# outdoor_module.net
KiCad netlist of a schematic drawn in EAGLE
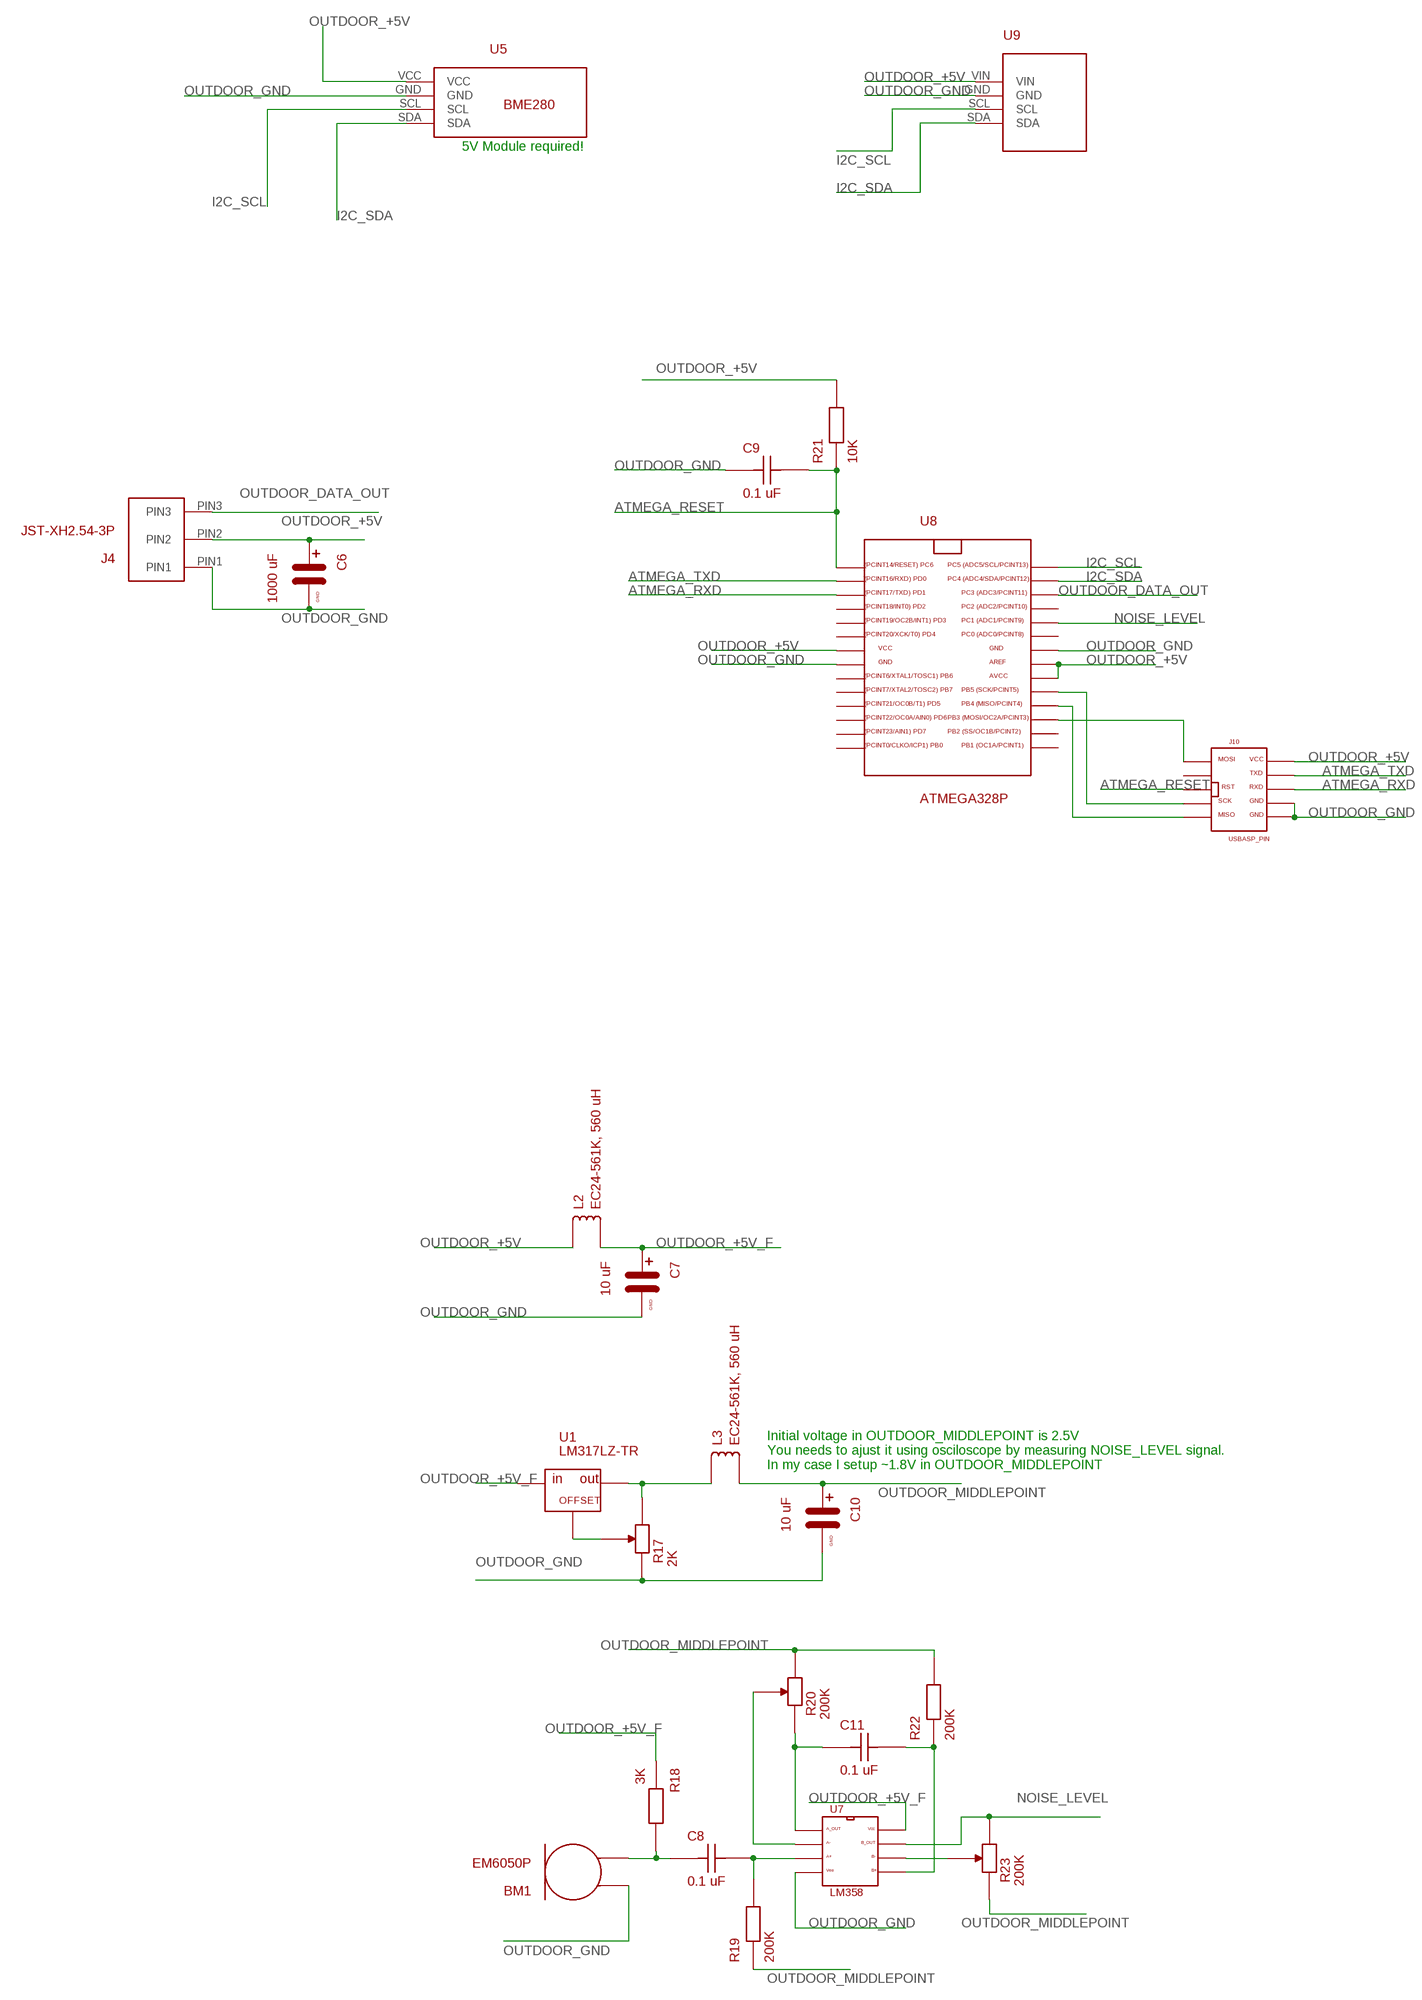
[diagram p0: schematic, sheet 1]

(export (version "E")
  (design (tool "Eeschema 10.0.6"))
  (components
    (comp (ref "BM1")
      (value "EM6050P")
      (footprint "eagle-import:MICROPHONE")
      (libsource (lib "eagle-import") (part "MICROPHONE"))
    )
    (comp (ref "C6")
      (value "1000 uF")
      (footprint "eagle-import:C")
      (libsource (lib "eagle-import") (part "C"))
    )
    (comp (ref "C7") (value "10 uF") (footprint "eagle-import:C") (libsource (lib "eagle-import") (part "C")))
    (comp (ref "C8")
      (value "0.1 uF")
      (footprint "eagle-import:C-1")
      (libsource (lib "eagle-import") (part "C-1"))
    )
    (comp (ref "C9")
      (value "0.1 uF")
      (footprint "eagle-import:C-1")
      (libsource (lib "eagle-import") (part "C-1"))
    )
    (comp (ref "C10")
      (value "10 uF")
      (footprint "eagle-import:C")
      (libsource (lib "eagle-import") (part "C"))
    )
    (comp (ref "C11")
      (value "0.1 uF")
      (footprint "eagle-import:C-1")
      (libsource (lib "eagle-import") (part "C-1"))
    )
    (comp (ref "J4")
      (value "JST-XH2.54-3P")
      (footprint "eagle-import:JST-XH254-3P")
      (libsource (lib "eagle-import") (part "JST-XH254-3P"))
    )
    (comp (ref "J10")
      (value "USBASP_PIN")
      (footprint "eagle-import:USBASP_PIN")
      (libsource (lib "eagle-import") (part "USBASP_PIN"))
    )
    (comp (ref "L2")
      (value "EC24-561K, 560 uH")
      (footprint "eagle-import:L-EC24")
      (libsource (lib "eagle-import") (part "LL-EC24"))
    )
    (comp (ref "L3")
      (value "EC24-561K, 560 uH")
      (footprint "eagle-import:L-EC24")
      (libsource (lib "eagle-import") (part "LL-EC24"))
    )
    (comp (ref "R17")
      (value "2K")
      (footprint "eagle-import:RD-3362H")
      (libsource (lib "eagle-import") (part "RD"))
    )
    (comp (ref "R18") (value "3K") (footprint "eagle-import:R") (libsource (lib "eagle-import") (part "R")))
    (comp (ref "R19") (value "200K") (footprint "eagle-import:R") (libsource (lib "eagle-import") (part "R")))
    (comp (ref "R20")
      (value "200K")
      (footprint "eagle-import:RD-3296Z")
      (libsource (lib "eagle-import") (part "RD3296-Z"))
    )
    (comp (ref "R21") (value "10K") (footprint "eagle-import:R") (libsource (lib "eagle-import") (part "R")))
    (comp (ref "R22") (value "200K") (footprint "eagle-import:R") (libsource (lib "eagle-import") (part "R")))
    (comp (ref "R23")
      (value "200K")
      (footprint "eagle-import:RD-3296Z")
      (libsource (lib "eagle-import") (part "RD3296-Z"))
    )
    (comp (ref "U1")
      (value "LM317LZ-TR")
      (footprint "eagle-import:TO-92")
      (libsource (lib "eagle-import") (part "LM317L"))
    )
    (comp (ref "U5")
      (value "BMP280 5V module")
      (footprint "eagle-import:BME280-CONNECTOR-ONLY")
      (libsource (lib "eagle-import") (part "BME280BME280-CONNECTOR-ONLY"))
    )
    (comp (ref "U7")
      (value "LM358")
      (footprint "eagle-import:DIP8")
      (libsource (lib "eagle-import") (part "LM358"))
    )
    (comp (ref "U8")
      (value "ATMEGA328P")
      (footprint "eagle-import:ATMEGA328P")
      (libsource (lib "eagle-import") (part "ATMEGA328P"))
    )
    (comp (ref "U9")
      (value "GY-SGP30")
      (footprint "eagle-import:GY-SGP30")
      (libsource (lib "eagle-import") (part "GY-SGP30"))
    )
  )
  (nets
    (net (code "1") (name "/ATMEGA_RESET") (class "Default")
      (node (ref "C9") (pin "P$2") (pinfunction "P$2_P$2") (pintype "bidirectional"))
      (node (ref "J10") (pin "RST") (pinfunction "RESET_RST") (pintype "bidirectional"))
      (node (ref "R21") (pin "P$1") (pinfunction "P$1_P$1") (pintype "bidirectional"))
      (node (ref "U8") (pin "PC6") (pinfunction "PC6_PC6") (pintype "bidirectional"))
    )
    (net (code "2") (name "/ATMEGA_RXD") (class "Default")
      (node (ref "J10") (pin "RXD") (pinfunction "RXD_RXD") (pintype "bidirectional"))
      (node (ref "U8") (pin "PD1") (pinfunction "PD1_PD1") (pintype "bidirectional"))
    )
    (net (code "3") (name "/ATMEGA_TXD") (class "Default")
      (node (ref "J10") (pin "TXD") (pinfunction "TXD_TXD") (pintype "bidirectional"))
      (node (ref "U8") (pin "PD0") (pinfunction "PD0_PD0") (pintype "bidirectional"))
    )
    (net (code "4") (name "/I2C_SCL") (class "Default")
      (node (ref "U5") (pin "SCL") (pinfunction "SCL_SCL") (pintype "bidirectional"))
      (node (ref "U8") (pin "PC5") (pinfunction "PC5_PC5") (pintype "bidirectional"))
      (node (ref "U9") (pin "SCL") (pinfunction "SCL_SCL") (pintype "bidirectional"))
    )
    (net (code "5") (name "/I2C_SDA") (class "Default")
      (node (ref "U5") (pin "SDA") (pinfunction "SDA_SDA") (pintype "bidirectional"))
      (node (ref "U8") (pin "PC4") (pinfunction "PC4_PC4") (pintype "bidirectional"))
      (node (ref "U9") (pin "SDA") (pinfunction "SDA_SDA") (pintype "bidirectional"))
    )
    (net (code "6") (name "/NOISE_LEVEL") (class "Default")
      (node (ref "R23") (pin "P2") (pinfunction "P2_P2") (pintype "bidirectional"))
      (node (ref "U7") (pin "PIN_7") (pinfunction "B_OUT_PIN_7") (pintype "output"))
      (node (ref "U8") (pin "PC1") (pinfunction "PC1_PC1") (pintype "bidirectional"))
    )
    (net (code "7") (name "/OUTDOOR_+5V") (class "Default")
      (node (ref "C6") (pin "PIN_PLUS") (pinfunction "PIN_PLUS_PIN_PLUS") (pintype "bidirectional"))
      (node (ref "J10") (pin "VCC") (pinfunction "VCC_VCC") (pintype "power_in"))
      (node (ref "J4") (pin "PIN2") (pinfunction "PIN2_PIN2") (pintype "bidirectional"))
      (node (ref "L2") (pin "P$1") (pinfunction "P$1_P$1") (pintype "bidirectional"))
      (node (ref "R21") (pin "P$2") (pinfunction "P$2_P$2") (pintype "bidirectional"))
      (node (ref "U5") (pin "VCC") (pinfunction "VCC_VCC") (pintype "power_in"))
      (node (ref "U8") (pin "AREF") (pinfunction "AREF_AREF") (pintype "bidirectional"))
      (node (ref "U8") (pin "AVCC") (pinfunction "AVCC_AVCC") (pintype "power_in"))
      (node (ref "U8") (pin "VCC") (pinfunction "VCC_VCC") (pintype "power_in"))
      (node (ref "U9") (pin "VIN") (pinfunction "VIN_VIN") (pintype "power_in"))
    )
    (net (code "8") (name "/OUTDOOR_+5V_F") (class "Default")
      (node (ref "C7") (pin "PIN_PLUS") (pinfunction "PIN_PLUS_PIN_PLUS") (pintype "bidirectional"))
      (node (ref "L2") (pin "P$2") (pinfunction "P$2_P$2") (pintype "bidirectional"))
      (node (ref "R18") (pin "P$1") (pinfunction "P$1_P$1") (pintype "bidirectional"))
      (node (ref "U1") (pin "P1") (pinfunction "IN_P1") (pintype "power_in"))
      (node (ref "U7") (pin "PIN_8") (pinfunction "VCC_PIN_8") (pintype "power_in"))
    )
    (net (code "9") (name "/OUTDOOR_DATA_OUT") (class "Default")
      (node (ref "J4") (pin "PIN3") (pinfunction "PIN3_PIN3") (pintype "bidirectional"))
      (node (ref "U8") (pin "PC3") (pinfunction "PC3_PC3") (pintype "bidirectional"))
    )
    (net (code "10") (name "/OUTDOOR_GND") (class "Default")
      (node (ref "BM1") (pin "P$1") (pinfunction "P$1_P$1") (pintype "bidirectional"))
      (node (ref "C10") (pin "PIN_GND") (pinfunction "PIN_GND_PIN_GND") (pintype "bidirectional"))
      (node (ref "C6") (pin "PIN_GND") (pinfunction "PIN_GND_PIN_GND") (pintype "bidirectional"))
      (node (ref "C7") (pin "PIN_GND") (pinfunction "PIN_GND_PIN_GND") (pintype "bidirectional"))
      (node (ref "C9") (pin "P$1") (pinfunction "P$1_P$1") (pintype "bidirectional"))
      (node (ref "J10") (pin "GND") (pinfunction "GND_GND") (pintype "power_in"))
      (node (ref "J10") (pin "GND1") (pinfunction "GND1_GND1") (pintype "power_in"))
      (node (ref "J4") (pin "PIN1") (pinfunction "PIN1_PIN1") (pintype "bidirectional"))
      (node (ref "R17") (pin "P1") (pinfunction "P1_P1") (pintype "bidirectional"))
      (node (ref "U5") (pin "GND") (pinfunction "GND_GND") (pintype "power_in"))
      (node (ref "U7") (pin "PIN_4") (pinfunction "VEE_PIN_4") (pintype "power_in"))
      (node (ref "U8") (pin "GND") (pinfunction "GND_GND") (pintype "power_in"))
      (node (ref "U8") (pin "GND1") (pinfunction "GND1_GND1") (pintype "power_in"))
      (node (ref "U9") (pin "GND") (pinfunction "GND_GND") (pintype "power_in"))
    )
    (net (code "11") (name "/OUTDOOR_MIDDLEPOINT") (class "Default")
      (node (ref "C10") (pin "PIN_PLUS") (pinfunction "PIN_PLUS_PIN_PLUS") (pintype "bidirectional"))
      (node (ref "L3") (pin "P$2") (pinfunction "P$2_P$2") (pintype "bidirectional"))
      (node (ref "R19") (pin "P$1") (pinfunction "P$1_P$1") (pintype "bidirectional"))
      (node (ref "R20") (pin "P2") (pinfunction "P2_P2") (pintype "bidirectional"))
      (node (ref "R22") (pin "P$2") (pinfunction "P$2_P$2") (pintype "bidirectional"))
      (node (ref "R23") (pin "P1") (pinfunction "P1_P1") (pintype "bidirectional"))
    )
    (net (code "12") (name "Net-(BM1-PadP$2)") (class "Default")
      (node (ref "BM1") (pin "P$2") (pinfunction "P$2_P$2") (pintype "bidirectional"))
      (node (ref "C8") (pin "P$1") (pinfunction "P$1_P$1") (pintype "bidirectional"))
      (node (ref "R18") (pin "P$2") (pinfunction "P$2_P$2") (pintype "bidirectional"))
    )
    (net (code "13") (name "Net-(J10-PadMISO)") (class "Default")
      (node (ref "J10") (pin "MISO") (pinfunction "MISO_MISO") (pintype "bidirectional"))
      (node (ref "U8") (pin "PB4") (pinfunction "PB4_PB4") (pintype "bidirectional"))
    )
    (net (code "14") (name "Net-(J10-PadMOSI)") (class "Default")
      (node (ref "J10") (pin "MOSI") (pinfunction "MOSI_MOSI") (pintype "bidirectional"))
      (node (ref "U8") (pin "PB3") (pinfunction "PB3_PB3") (pintype "bidirectional"))
    )
    (net (code "15") (name "Net-(J10-PadSCK)") (class "Default")
      (node (ref "J10") (pin "SCK") (pinfunction "SCK_SCK") (pintype "bidirectional"))
      (node (ref "U8") (pin "PB5") (pinfunction "PB5_PB5") (pintype "bidirectional"))
    )
    (net (code "16") (name "Net-(U1-GND)") (class "Default")
      (node (ref "R17") (pin "P3") (pinfunction "P3_P3") (pintype "bidirectional"))
      (node (ref "U1") (pin "P3") (pinfunction "GND_P3") (pintype "power_in"))
    )
    (net (code "17") (name "Net-(U1-OUT)") (class "Default")
      (node (ref "L3") (pin "P$1") (pinfunction "P$1_P$1") (pintype "bidirectional"))
      (node (ref "R17") (pin "P2") (pinfunction "P2_P2") (pintype "bidirectional"))
      (node (ref "U1") (pin "P2") (pinfunction "OUT_P2") (pintype "power_in"))
    )
    (net (code "18") (name "Net-(U7-A+)") (class "Default")
      (node (ref "C8") (pin "P$2") (pinfunction "P$2_P$2") (pintype "bidirectional"))
      (node (ref "R19") (pin "P$2") (pinfunction "P$2_P$2") (pintype "bidirectional"))
      (node (ref "U7") (pin "PIN_3") (pinfunction "A+_PIN_3") (pintype "input"))
    )
    (net (code "19") (name "Net-(U7-A-)") (class "Default")
      (node (ref "R20") (pin "P3") (pinfunction "P3_P3") (pintype "bidirectional"))
      (node (ref "U7") (pin "PIN_2") (pinfunction "A-_PIN_2") (pintype "input"))
    )
    (net (code "20") (name "Net-(U7-A_OUT)") (class "Default")
      (node (ref "C11") (pin "P$1") (pinfunction "P$1_P$1") (pintype "bidirectional"))
      (node (ref "R20") (pin "P1") (pinfunction "P1_P1") (pintype "bidirectional"))
      (node (ref "U7") (pin "PIN_1") (pinfunction "A_OUT_PIN_1") (pintype "output"))
    )
    (net (code "21") (name "Net-(U7-B+)") (class "Default")
      (node (ref "C11") (pin "P$2") (pinfunction "P$2_P$2") (pintype "bidirectional"))
      (node (ref "R22") (pin "P$1") (pinfunction "P$1_P$1") (pintype "bidirectional"))
      (node (ref "U7") (pin "PIN_5") (pinfunction "B+_PIN_5") (pintype "input"))
    )
    (net (code "22") (name "Net-(U7-B-)") (class "Default")
      (node (ref "R23") (pin "P3") (pinfunction "P3_P3") (pintype "bidirectional"))
      (node (ref "U7") (pin "PIN_6") (pinfunction "B-_PIN_6") (pintype "input"))
    )
    (net (code "23") (name "unconnected-(J10-PadNC1)") (class "Default")
      (node (ref "J10") (pin "NC1") (pinfunction "NC1_NC1") (pintype "no_connect"))
    )
    (net (code "24") (name "unconnected-(U8-PadPB0)") (class "Default")
      (node (ref "U8") (pin "PB0") (pinfunction "PB0_PB0") (pintype "bidirectional"))
    )
    (net (code "25") (name "unconnected-(U8-PadPB1)") (class "Default")
      (node (ref "U8") (pin "PB1") (pinfunction "PB1_PB1") (pintype "bidirectional"))
    )
    (net (code "26") (name "unconnected-(U8-PadPB2)") (class "Default")
      (node (ref "U8") (pin "PB2") (pinfunction "PB2_PB2") (pintype "bidirectional"))
    )
    (net (code "27") (name "unconnected-(U8-PadPB6)") (class "Default")
      (node (ref "U8") (pin "PB6") (pinfunction "PB6_PB6") (pintype "bidirectional"))
    )
    (net (code "28") (name "unconnected-(U8-PadPB7)") (class "Default")
      (node (ref "U8") (pin "PB7") (pinfunction "PB7_PB7") (pintype "bidirectional"))
    )
    (net (code "29") (name "unconnected-(U8-PadPC0)") (class "Default")
      (node (ref "U8") (pin "PC0") (pinfunction "PC0_PC0") (pintype "bidirectional"))
    )
    (net (code "30") (name "unconnected-(U8-PadPC2)") (class "Default")
      (node (ref "U8") (pin "PC2") (pinfunction "PC2_PC2") (pintype "bidirectional"))
    )
    (net (code "31") (name "unconnected-(U8-PadPD2)") (class "Default")
      (node (ref "U8") (pin "PD2") (pinfunction "PD2_PD2") (pintype "bidirectional"))
    )
    (net (code "32") (name "unconnected-(U8-PadPD3)") (class "Default")
      (node (ref "U8") (pin "PD3") (pinfunction "PD3_PD3") (pintype "bidirectional"))
    )
    (net (code "33") (name "unconnected-(U8-PadPD4)") (class "Default")
      (node (ref "U8") (pin "PD4") (pinfunction "PD4_PD4") (pintype "bidirectional"))
    )
    (net (code "34") (name "unconnected-(U8-PadPD5)") (class "Default")
      (node (ref "U8") (pin "PD5") (pinfunction "PD5_PD5") (pintype "bidirectional"))
    )
    (net (code "35") (name "unconnected-(U8-PadPD6)") (class "Default")
      (node (ref "U8") (pin "PD6") (pinfunction "PD6_PD6") (pintype "bidirectional"))
    )
    (net (code "36") (name "unconnected-(U8-PadPD7)") (class "Default")
      (node (ref "U8") (pin "PD7") (pinfunction "PD7_PD7") (pintype "bidirectional"))
    )
  )
)
